# MP-Power.net
KiCad netlist of a schematic drawn in Altium Designer
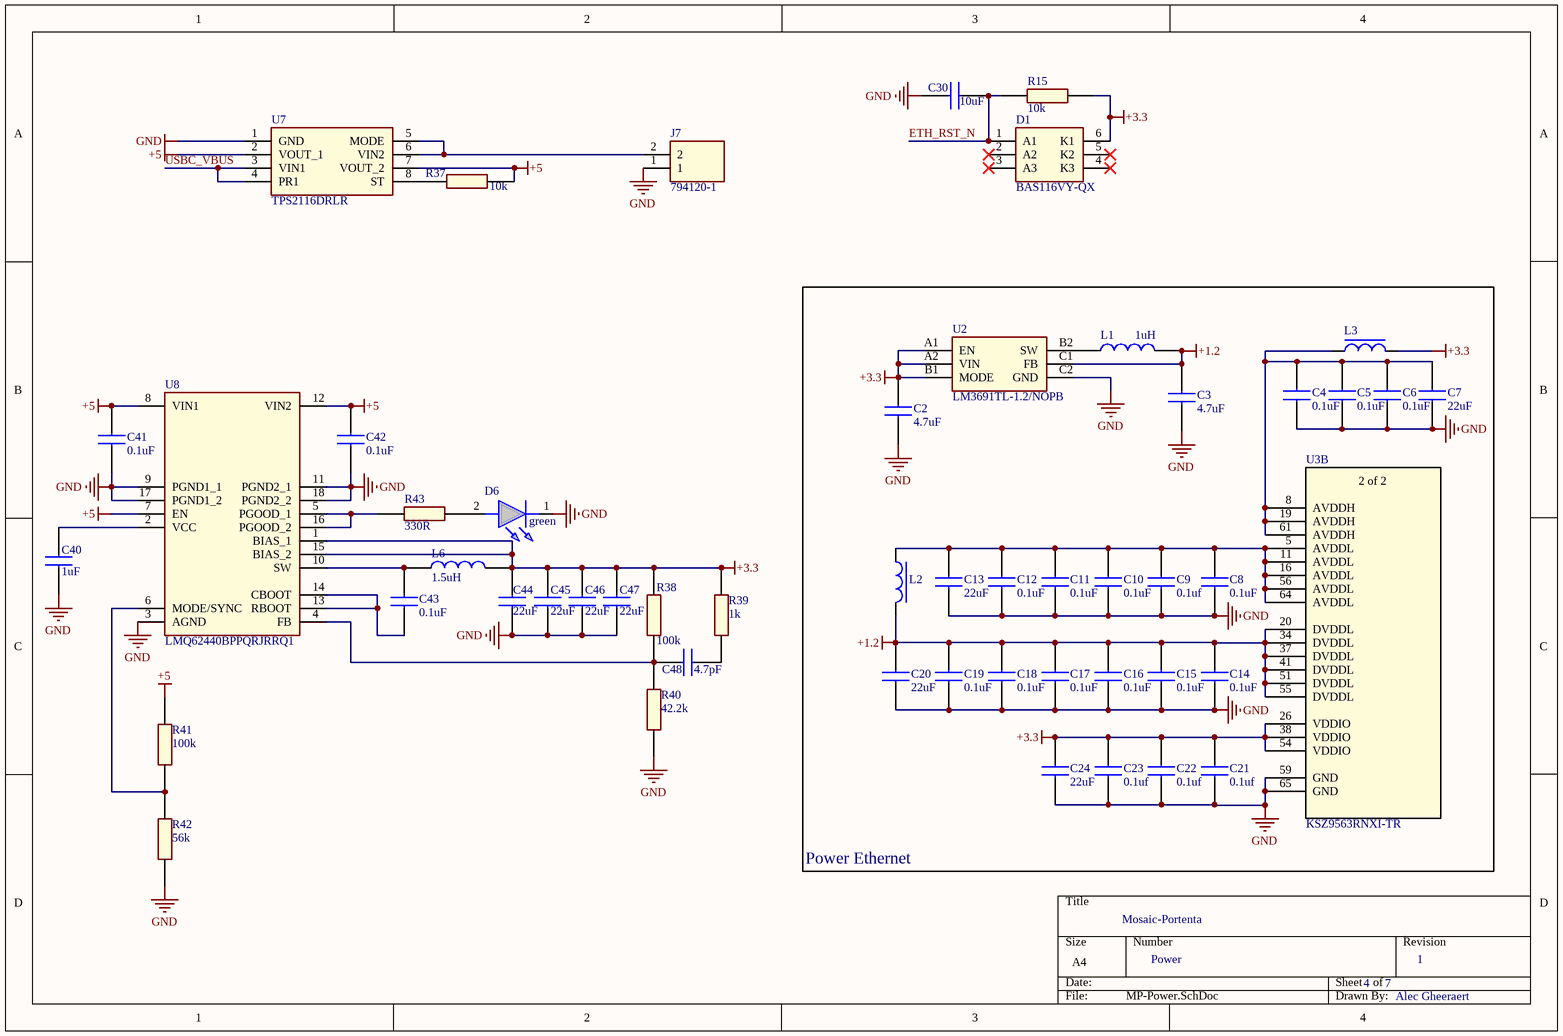
[diagram p0: MP-Power.SchDoc]

(export (version "E")
  (design (tool "Eeschema 10.0.6"))
  (components
    (comp (ref "C2")
      (value "4.7uF")
      (footprint "CAPC1608X100N")
      (description "0603 4.7µF")
      (fields (field (name "MANUFACTURER") "Walsin") (field (name "TOLERANCE") "20%"))
      (libsource (lib "Ghrt") (part "0603X475M6R3CT"))
    )
    (comp (ref "C3")
      (value "4.7uF")
      (footprint "CAPC1608X100N")
      (description "0603 4.7µF")
      (fields (field (name "MANUFACTURER") "Walsin") (field (name "TOLERANCE") "20%"))
      (libsource (lib "Ghrt") (part "0603X475M6R3CT"))
    )
    (comp (ref "C4")
      (value "0.1uF")
      (footprint "CAPC1005X55N")
      (description "0402I 0.1µF")
      (fields (field (name "MANUFACTURER") "Walsin") (field (name "TOLERANCE") "10%"))
      (libsource (lib "Ghrt") (part "MG15B104K100CT"))
    )
    (comp (ref "C5")
      (value "0.1uF")
      (footprint "CAPC1005X55N")
      (description "0402I 0.1µF")
      (fields (field (name "MANUFACTURER") "Walsin") (field (name "TOLERANCE") "10%"))
      (libsource (lib "Ghrt") (part "MG15B104K100CT"))
    )
    (comp (ref "C6")
      (value "0.1uF")
      (footprint "CAPC1005X55N")
      (description "0402I 0.1µF")
      (fields (field (name "MANUFACTURER") "Walsin") (field (name "TOLERANCE") "10%"))
      (libsource (lib "Ghrt") (part "MG15B104K100CT"))
    )
    (comp (ref "C7")
      (value "22uF")
      (footprint "CAPC2012X145N")
      (description "0805 22µF")
      (fields (field (name "MANUFACTURER") "Walsin") (field (name "TOLERANCE") "10%"))
      (libsource (lib "Ghrt") (part "0805X226K6R3CT"))
    )
    (comp (ref "C8")
      (value "0.1uF")
      (footprint "CAPC1005X55N")
      (description "0402I 0.1µF")
      (fields (field (name "MANUFACTURER") "Walsin") (field (name "TOLERANCE") "10%"))
      (libsource (lib "Ghrt") (part "MG15B104K100CT"))
    )
    (comp (ref "C9")
      (value "0.1uf")
      (footprint "CAPC1005X55N")
      (description "0402I 0.1µF")
      (fields (field (name "MANUFACTURER") "Walsin") (field (name "TOLERANCE") "10%"))
      (libsource (lib "Ghrt") (part "MG15B104K100CT"))
    )
    (comp (ref "C10")
      (value "0.1uF")
      (footprint "CAPC1005X55N")
      (description "0402I 0.1µF")
      (fields (field (name "MANUFACTURER") "Walsin") (field (name "TOLERANCE") "10%"))
      (libsource (lib "Ghrt") (part "MG15B104K100CT"))
    )
    (comp (ref "C11")
      (value "0.1uF")
      (footprint "CAPC1005X55N")
      (description "0402I 0.1µF")
      (fields (field (name "MANUFACTURER") "Walsin") (field (name "TOLERANCE") "10%"))
      (libsource (lib "Ghrt") (part "MG15B104K100CT"))
    )
    (comp (ref "C12")
      (value "0.1uF")
      (footprint "CAPC1005X55N")
      (description "0402I 0.1µF")
      (fields (field (name "MANUFACTURER") "Walsin") (field (name "TOLERANCE") "10%"))
      (libsource (lib "Ghrt") (part "MG15B104K100CT"))
    )
    (comp (ref "C13")
      (value "22uF")
      (footprint "CAPC2012X145N")
      (description "0805 22µF")
      (fields (field (name "MANUFACTURER") "Walsin") (field (name "TOLERANCE") "10%"))
      (libsource (lib "Ghrt") (part "0805X226K6R3CT"))
    )
    (comp (ref "C14")
      (value "0.1uF")
      (footprint "CAPC1005X55N")
      (description "0402I 0.1µF")
      (fields (field (name "MANUFACTURER") "Walsin") (field (name "TOLERANCE") "10%"))
      (libsource (lib "Ghrt") (part "MG15B104K100CT"))
    )
    (comp (ref "C15")
      (value "0.1uF")
      (footprint "CAPC1005X55N")
      (description "0402I 0.1µF")
      (fields (field (name "MANUFACTURER") "Walsin") (field (name "TOLERANCE") "10%"))
      (libsource (lib "Ghrt") (part "MG15B104K100CT"))
    )
    (comp (ref "C16")
      (value "0.1uF")
      (footprint "CAPC1005X55N")
      (description "0402I 0.1µF")
      (fields (field (name "MANUFACTURER") "Walsin") (field (name "TOLERANCE") "10%"))
      (libsource (lib "Ghrt") (part "MG15B104K100CT"))
    )
    (comp (ref "C17")
      (value "0.1uF")
      (footprint "CAPC1005X55N")
      (description "0402I 0.1µF")
      (fields (field (name "MANUFACTURER") "Walsin") (field (name "TOLERANCE") "10%"))
      (libsource (lib "Ghrt") (part "MG15B104K100CT"))
    )
    (comp (ref "C18")
      (value "0.1uF")
      (footprint "CAPC1005X55N")
      (description "0402I 0.1µF")
      (fields (field (name "MANUFACTURER") "Walsin") (field (name "TOLERANCE") "10%"))
      (libsource (lib "Ghrt") (part "MG15B104K100CT"))
    )
    (comp (ref "C19")
      (value "0.1uF")
      (footprint "CAPC1005X55N")
      (description "0402I 0.1µF")
      (fields (field (name "MANUFACTURER") "Walsin") (field (name "TOLERANCE") "10%"))
      (libsource (lib "Ghrt") (part "MG15B104K100CT"))
    )
    (comp (ref "C20")
      (value "22uF")
      (footprint "CAPC2012X145N")
      (description "0805 22µF")
      (fields (field (name "MANUFACTURER") "Walsin") (field (name "TOLERANCE") "10%"))
      (libsource (lib "Ghrt") (part "0805X226K6R3CT"))
    )
    (comp (ref "C21")
      (value "0.1uf")
      (footprint "CAPC1005X55N")
      (description "0402I 0.1µF")
      (fields (field (name "MANUFACTURER") "Walsin") (field (name "TOLERANCE") "10%"))
      (libsource (lib "Ghrt") (part "MG15B104K100CT"))
    )
    (comp (ref "C22")
      (value "0.1uf")
      (footprint "CAPC1005X55N")
      (description "0402I 0.1µF")
      (fields (field (name "MANUFACTURER") "Walsin") (field (name "TOLERANCE") "10%"))
      (libsource (lib "Ghrt") (part "MG15B104K100CT"))
    )
    (comp (ref "C23")
      (value "0.1uf")
      (footprint "CAPC1005X55N")
      (description "0402I 0.1µF")
      (fields (field (name "MANUFACTURER") "Walsin") (field (name "TOLERANCE") "10%"))
      (libsource (lib "Ghrt") (part "MG15B104K100CT"))
    )
    (comp (ref "C24")
      (value "22uF")
      (footprint "CAPC2012X145N")
      (description "0805 22µF")
      (fields (field (name "MANUFACTURER") "Walsin") (field (name "TOLERANCE") "10%"))
      (libsource (lib "Ghrt") (part "0805X226K6R3CT"))
    )
    (comp (ref "C30")
      (value "10uF")
      (footprint "CAPC1608X100N")
      (description "0603 10µF")
      (fields (field (name "MANUFACTURER") "Walsin") (field (name "TOLERANCE") "10%"))
      (libsource (lib "Ghrt") (part "0603X106K6R3CT"))
    )
    (comp (ref "C40")
      (value "1uF")
      (footprint "CAPC1608X100N")
      (description "0603 1µF")
      (fields (field (name "MANUFACTURER") "Walsin") (field (name "TOLERANCE") "10%"))
      (libsource (lib "Ghrt") (part "0603X105K6R3CT"))
    )
    (comp (ref "C41")
      (value "0.1uF")
      (footprint "CAPC2012X145N")
      (description "0805I 0.1µF")
      (fields (field (name "MANUFACTURER") "Walsin") (field (name "TOLERANCE") "10%"))
      (libsource (lib "Ghrt") (part "MG21B104K101CT"))
    )
    (comp (ref "C42")
      (value "0.1uF")
      (footprint "CAPC2012X145N")
      (description "0805I 0.1µF")
      (fields (field (name "MANUFACTURER") "Walsin") (field (name "TOLERANCE") "10%"))
      (libsource (lib "Ghrt") (part "MG21B104K101CT"))
    )
    (comp (ref "C43")
      (value "0.1uF")
      (footprint "CAPC1005X55N")
      (description "0402I 0.1µF")
      (fields (field (name "MANUFACTURER") "Walsin") (field (name "TOLERANCE") "10%"))
      (libsource (lib "Ghrt") (part "MG15B104K100CT"))
    )
    (comp (ref "C44")
      (value "22uF")
      (footprint "CAPC2012X145N")
      (description "0805 22µF")
      (fields (field (name "MANUFACTURER") "Walsin") (field (name "TOLERANCE") "10%"))
      (libsource (lib "Ghrt") (part "0805X226K6R3CT"))
    )
    (comp (ref "C45")
      (value "22uF")
      (footprint "CAPC2012X145N")
      (description "0805 22µF")
      (fields (field (name "MANUFACTURER") "Walsin") (field (name "TOLERANCE") "10%"))
      (libsource (lib "Ghrt") (part "0805X226K6R3CT"))
    )
    (comp (ref "C46")
      (value "22uF")
      (footprint "CAPC2012X145N")
      (description "0805 22µF")
      (fields (field (name "MANUFACTURER") "Walsin") (field (name "TOLERANCE") "10%"))
      (libsource (lib "Ghrt") (part "0805X226K6R3CT"))
    )
    (comp (ref "C47")
      (value "22uF")
      (footprint "CAPC2012X145N")
      (description "0805 22µF")
      (fields (field (name "MANUFACTURER") "Walsin") (field (name "TOLERANCE") "10%"))
      (libsource (lib "Ghrt") (part "0805X226K6R3CT"))
    )
    (comp (ref "C48")
      (value "4.7pF")
      (footprint "CAPC1608X87N")
      (description "0603 4.7pF")
      (fields (field (name "TOLERANCE") "5%") (field (name "MANUFACTURER") "Walsin"))
      (libsource (lib "Ghrt") (part "0603N4R7B500CT"))
    )
    (comp (ref "D1")
      (value "BAS116VY-QX")
      (footprint "BAS116VYQX")
      (description "Triple Diode Array")
      (fields (field (name "MANUFACTURER") "Nexperia"))
      (libsource (lib "Ghrt") (part "BAS116VY-QX"))
    )
    (comp (ref "D6")
      (value "green")
      (footprint "APT1608ZGCAMT")
      (description "0603 Green LED")
      (libsource (lib "Ghrt") (part "APT1608ZGC-AMT"))
    )
    (comp (ref "J7")
      (value "794120-1")
      (footprint "7941201")
      (description "Right Angle PCB Header")
      (libsource (lib "Ghrt") (part "794120-1"))
    )
    (comp (ref "L1")
      (value "1uH")
      (footprint "INDC2016X100N")
      (description "1µH Inductor")
      (fields (field (name "TOLERANCE") "20%") (field (name "MANUFACTURER") "TDK"))
      (libsource (lib "Ghrt") (part "MLP2016H1R0MT0S1"))
    )
    (comp (ref "L2")
      (value "MPZ1608S121ATDH5")
      (footprint "BEADC1608X75N")
      (description "0603I 120ohms Ferrite Bead")
      (fields (field (name "TOLERANCE") "25%") (field (name "MANUFACTURER") "TDK"))
      (libsource (lib "Ghrt") (part "MPZ1608S121ATDH5"))
    )
    (comp (ref "L3")
      (value "MPZ1608S121ATDH5")
      (footprint "BEADC1608X75N")
      (description "0603I 120ohms Ferrite Bead")
      (fields (field (name "TOLERANCE") "25%") (field (name "MANUFACTURER") "TDK"))
      (libsource (lib "Ghrt") (part "MPZ1608S121ATDH5"))
    )
    (comp (ref "L6")
      (value "1.5uH")
      (footprint "INDC1005X55N")
      (description "1.5uH Inductor")
      (libsource (lib "Ghrt") (part "MLF1005G1R5JTD25"))
    )
    (comp (ref "R15")
      (value "10k")
      (footprint "RESC1005X40N")
      (description "0402I 10k")
      (fields (field (name "MANUFACTURER") "Walsin") (field (name "TOLERANCE") "1%"))
      (libsource (lib "") (part "WR04X1002FTL_1"))
    )
    (comp (ref "R37")
      (value "10k")
      (footprint "RESC1005X40N")
      (description "0402I 10k")
      (fields (field (name "MANUFACTURER") "Walsin") (field (name "TOLERANCE") "1%"))
      (libsource (lib "Ghrt") (part "WR04X1002FTL"))
    )
    (comp (ref "R38")
      (value "100k")
      (footprint "RESC1005X40N")
      (description "0402I 100k")
      (fields (field (name "MANUFACTURER") "Walsin") (field (name "TOLERANCE") "1%"))
      (libsource (lib "Ghrt") (part "WR04X1003FTL"))
    )
    (comp (ref "R39")
      (value "1k")
      (footprint "RESC1005X40N")
      (description "0402I 1k")
      (fields (field (name "MANUFACTURER") "Walsin") (field (name "TOLERANCE") "1%"))
      (libsource (lib "Ghrt") (part "WR04X1001FTL"))
    )
    (comp (ref "R40")
      (value "42.2k")
      (footprint "RESC1005X40N")
      (description "0402I 42.2k")
      (fields (field (name "TOLERANCE") "1%") (field (name "MANUFACTURER") "Walsin"))
      (libsource (lib "Ghrt") (part "WR04X4222FTL"))
    )
    (comp (ref "R41")
      (value "100k")
      (footprint "RESC1005X40N")
      (description "0402I 100k")
      (fields (field (name "MANUFACTURER") "Walsin") (field (name "TOLERANCE") "1%"))
      (libsource (lib "") (part "WR04X1003FTL_1"))
    )
    (comp (ref "R42")
      (value "56k")
      (footprint "RESC1005X40N")
      (description "0402I 56k")
      (fields (field (name "TOLERANCE") "1%") (field (name "MANUFACTURER") "Walsin"))
      (libsource (lib "Ghrt") (part "WR04X5602FTL"))
    )
    (comp (ref "R43")
      (value "330R")
      (footprint "RESC1005X40N")
      (description "0402I 330")
      (fields (field (name "TOLERANCE") "1%") (field (name "MANUFACTURER") "Walsin"))
      (libsource (lib "Ghrt") (part "WR04X3300FTL"))
    )
    (comp (ref "U2")
      (value "LM3691TL-1.2/NOPB")
      (footprint "BGA6C50P2X3_126X156X68")
      (description "1.2V 1A Buck Converter")
      (fields (field (name "MANUFACTURER") "Texas Instruments"))
      (libsource (lib "Ghrt") (part "LM3691TL-1.2_NOPB"))
    )
    (comp (ref "U3")
      (value "KSZ9563RNXI-TR")
      (footprint "VQFN64_NX_MCH")
      (description "3-Port Gigabit Ethernet Switch")
      (fields (field (name "MANUFACTURER") "Texas Instruments"))
      (libsource (lib "Ghrt") (part "KSZ9563RNXI-TR"))
    )
    (comp (ref "U7")
      (value "TPS2116DRLR")
      (footprint "SOTFL50P160X60-8N")
      (description "2.5A Power Multiplexer")
      (fields (field (name "MANUFACTURER") "Texas Instruments"))
      (libsource (lib "Ghrt") (part "TPS2116DRLR"))
    )
    (comp (ref "U8")
      (value "LMQ62440BPPQRJRRQ1")
      (footprint "LMQ62440BPPQRJRRQ1")
      (description "3.3V 4A Switching Voltage Regulator")
      (fields (field (name "MANUFACTURER") "Texas Instruments"))
      (libsource (lib "Ghrt") (part "LMQ62440BPPQRJRRQ1"))
    )
  )
  (nets
    (net (code "1") (name "+1.2") (class "Default")
      (node (ref "C14") (pin "1") (pinfunction "1_1") (pintype "passive"))
      (node (ref "C15") (pin "1") (pinfunction "1_1") (pintype "passive"))
      (node (ref "C16") (pin "1") (pinfunction "1_1") (pintype "passive"))
      (node (ref "C17") (pin "1") (pinfunction "1_1") (pintype "passive"))
      (node (ref "C18") (pin "1") (pinfunction "1_1") (pintype "passive"))
      (node (ref "C19") (pin "1") (pinfunction "1_1") (pintype "passive"))
      (node (ref "C20") (pin "1") (pinfunction "1_1") (pintype "passive"))
      (node (ref "C3") (pin "1") (pinfunction "1_1") (pintype "passive"))
      (node (ref "L1") (pin "2") (pinfunction "2_2") (pintype "passive"))
      (node (ref "L2") (pin "2") (pinfunction "2_2") (pintype "passive"))
      (node (ref "U2") (pin "C1") (pinfunction "FB_C1") (pintype "passive"))
      (node (ref "U3") (pin "20") (pinfunction "DVDDL_20") (pintype "power_in"))
      (node (ref "U3") (pin "34") (pinfunction "DVDDL_34") (pintype "power_in"))
      (node (ref "U3") (pin "37") (pinfunction "DVDDL_37") (pintype "power_in"))
      (node (ref "U3") (pin "41") (pinfunction "DVDDL_41") (pintype "power_in"))
      (node (ref "U3") (pin "51") (pinfunction "DVDDL_51") (pintype "power_in"))
      (node (ref "U3") (pin "55") (pinfunction "DVDDL_55") (pintype "power_in"))
    )
    (net (code "2") (name "+3.3") (class "Default")
      (node (ref "C2") (pin "1") (pinfunction "1_1") (pintype "passive"))
      (node (ref "C21") (pin "1") (pinfunction "1_1") (pintype "passive"))
      (node (ref "C22") (pin "1") (pinfunction "1_1") (pintype "passive"))
      (node (ref "C23") (pin "1") (pinfunction "1_1") (pintype "passive"))
      (node (ref "C24") (pin "1") (pinfunction "1_1") (pintype "passive"))
      (node (ref "C44") (pin "1") (pinfunction "1_1") (pintype "passive"))
      (node (ref "C45") (pin "1") (pinfunction "1_1") (pintype "passive"))
      (node (ref "C46") (pin "1") (pinfunction "1_1") (pintype "passive"))
      (node (ref "C47") (pin "1") (pinfunction "1_1") (pintype "passive"))
      (node (ref "D1") (pin "6") (pinfunction "K1_6") (pintype "passive"))
      (node (ref "L3") (pin "2") (pinfunction "2_2") (pintype "passive"))
      (node (ref "L6") (pin "2") (pinfunction "2_2") (pintype "passive"))
      (node (ref "R15") (pin "1") (pinfunction "1_1") (pintype "passive"))
      (node (ref "R38") (pin "1") (pinfunction "1_1") (pintype "passive"))
      (node (ref "R39") (pin "2") (pinfunction "2_2") (pintype "passive"))
      (node (ref "U2") (pin "A1") (pinfunction "EN_A1") (pintype "passive"))
      (node (ref "U2") (pin "A2") (pinfunction "VIN_A2") (pintype "passive"))
      (node (ref "U2") (pin "B1") (pinfunction "MODE_B1") (pintype "passive"))
      (node (ref "U3") (pin "26") (pinfunction "VDDIO_26") (pintype "power_in"))
      (node (ref "U3") (pin "38") (pinfunction "VDDIO_38") (pintype "power_in"))
      (node (ref "U3") (pin "54") (pinfunction "VDDIO_54") (pintype "power_in"))
      (node (ref "U8") (pin "1") (pinfunction "BIAS_1_1") (pintype "passive"))
      (node (ref "U8") (pin "15") (pinfunction "BIAS_2_15") (pintype "passive"))
    )
    (net (code "3") (name "+5") (class "Default")
      (node (ref "C41") (pin "1") (pinfunction "1_1") (pintype "passive"))
      (node (ref "C42") (pin "1") (pinfunction "1_1") (pintype "passive"))
      (node (ref "R37") (pin "2") (pinfunction "2_2") (pintype "passive"))
      (node (ref "R41") (pin "2") (pinfunction "2_2") (pintype "passive"))
      (node (ref "U7") (pin "2") (pinfunction "VOUT_1_2") (pintype "passive"))
      (node (ref "U7") (pin "7") (pinfunction "VOUT_2_7") (pintype "passive"))
      (node (ref "U8") (pin "12") (pinfunction "VIN2_12") (pintype "passive"))
      (node (ref "U8") (pin "7") (pinfunction "EN_7") (pintype "passive"))
      (node (ref "U8") (pin "8") (pinfunction "VIN1_8") (pintype "passive"))
    )
    (net (code "4") (name "/ETH_RST_N") (class "Default")
      (node (ref "C30") (pin "1") (pinfunction "1_1") (pintype "passive"))
      (node (ref "D1") (pin "1") (pinfunction "A1_1") (pintype "passive"))
      (node (ref "R15") (pin "2") (pinfunction "2_2") (pintype "passive"))
    )
    (net (code "5") (name "/USBC_VBUS") (class "Default")
      (node (ref "U7") (pin "3") (pinfunction "VIN1_3") (pintype "passive"))
      (node (ref "U7") (pin "4") (pinfunction "PR1_4") (pintype "passive"))
    )
    (net (code "6") (name "GND") (class "Default")
      (node (ref "C10") (pin "2") (pinfunction "2_2") (pintype "passive"))
      (node (ref "C11") (pin "2") (pinfunction "2_2") (pintype "passive"))
      (node (ref "C12") (pin "2") (pinfunction "2_2") (pintype "passive"))
      (node (ref "C13") (pin "2") (pinfunction "2_2") (pintype "passive"))
      (node (ref "C14") (pin "2") (pinfunction "2_2") (pintype "passive"))
      (node (ref "C15") (pin "2") (pinfunction "2_2") (pintype "passive"))
      (node (ref "C16") (pin "2") (pinfunction "2_2") (pintype "passive"))
      (node (ref "C17") (pin "2") (pinfunction "2_2") (pintype "passive"))
      (node (ref "C18") (pin "2") (pinfunction "2_2") (pintype "passive"))
      (node (ref "C19") (pin "2") (pinfunction "2_2") (pintype "passive"))
      (node (ref "C2") (pin "2") (pinfunction "2_2") (pintype "passive"))
      (node (ref "C20") (pin "2") (pinfunction "2_2") (pintype "passive"))
      (node (ref "C21") (pin "2") (pinfunction "2_2") (pintype "passive"))
      (node (ref "C22") (pin "2") (pinfunction "2_2") (pintype "passive"))
      (node (ref "C23") (pin "2") (pinfunction "2_2") (pintype "passive"))
      (node (ref "C24") (pin "2") (pinfunction "2_2") (pintype "passive"))
      (node (ref "C3") (pin "2") (pinfunction "2_2") (pintype "passive"))
      (node (ref "C30") (pin "2") (pinfunction "2_2") (pintype "passive"))
      (node (ref "C4") (pin "2") (pinfunction "2_2") (pintype "passive"))
      (node (ref "C40") (pin "2") (pinfunction "2_2") (pintype "passive"))
      (node (ref "C41") (pin "2") (pinfunction "2_2") (pintype "passive"))
      (node (ref "C42") (pin "2") (pinfunction "2_2") (pintype "passive"))
      (node (ref "C44") (pin "2") (pinfunction "2_2") (pintype "passive"))
      (node (ref "C45") (pin "2") (pinfunction "2_2") (pintype "passive"))
      (node (ref "C46") (pin "2") (pinfunction "2_2") (pintype "passive"))
      (node (ref "C47") (pin "2") (pinfunction "2_2") (pintype "passive"))
      (node (ref "C5") (pin "2") (pinfunction "2_2") (pintype "passive"))
      (node (ref "C6") (pin "2") (pinfunction "2_2") (pintype "passive"))
      (node (ref "C7") (pin "2") (pinfunction "2_2") (pintype "passive"))
      (node (ref "C8") (pin "2") (pinfunction "2_2") (pintype "passive"))
      (node (ref "C9") (pin "2") (pinfunction "2_2") (pintype "passive"))
      (node (ref "D6") (pin "1") (pinfunction "K_1") (pintype "passive"))
      (node (ref "J7") (pin "1") (pinfunction "1_1") (pintype "passive"))
      (node (ref "R40") (pin "2") (pinfunction "2_2") (pintype "passive"))
      (node (ref "R42") (pin "2") (pinfunction "2_2") (pintype "passive"))
      (node (ref "U2") (pin "C2") (pinfunction "GND_C2") (pintype "passive"))
      (node (ref "U3") (pin "59") (pinfunction "GND_59") (pintype "power_in"))
      (node (ref "U3") (pin "65") (pinfunction "GND_65") (pintype "power_in"))
      (node (ref "U7") (pin "1") (pinfunction "GND_1") (pintype "passive"))
      (node (ref "U8") (pin "11") (pinfunction "PGND2_1_11") (pintype "passive"))
      (node (ref "U8") (pin "17") (pinfunction "PGND1_2_17") (pintype "passive"))
      (node (ref "U8") (pin "18") (pinfunction "PGND2_2_18") (pintype "passive"))
      (node (ref "U8") (pin "3") (pinfunction "AGND_3") (pintype "passive"))
      (node (ref "U8") (pin "9") (pinfunction "PGND1_1_9") (pintype "passive"))
    )
    (net (code "7") (name "Net-(C4-Pad1)") (class "Default")
      (node (ref "C4") (pin "1") (pinfunction "1_1") (pintype "passive"))
      (node (ref "C5") (pin "1") (pinfunction "1_1") (pintype "passive"))
      (node (ref "C6") (pin "1") (pinfunction "1_1") (pintype "passive"))
      (node (ref "C7") (pin "1") (pinfunction "1_1") (pintype "passive"))
      (node (ref "L3") (pin "1") (pinfunction "1_1") (pintype "passive"))
      (node (ref "U3") (pin "19") (pinfunction "AVDDH_19") (pintype "power_in"))
      (node (ref "U3") (pin "61") (pinfunction "AVDDH_61") (pintype "power_in"))
      (node (ref "U3") (pin "8") (pinfunction "AVDDH_8") (pintype "power_in"))
    )
    (net (code "8") (name "Net-(C10-Pad1)") (class "Default")
      (node (ref "C10") (pin "1") (pinfunction "1_1") (pintype "passive"))
      (node (ref "C11") (pin "1") (pinfunction "1_1") (pintype "passive"))
      (node (ref "C12") (pin "1") (pinfunction "1_1") (pintype "passive"))
      (node (ref "C13") (pin "1") (pinfunction "1_1") (pintype "passive"))
      (node (ref "C8") (pin "1") (pinfunction "1_1") (pintype "passive"))
      (node (ref "C9") (pin "1") (pinfunction "1_1") (pintype "passive"))
      (node (ref "L2") (pin "1") (pinfunction "1_1") (pintype "passive"))
      (node (ref "U3") (pin "11") (pinfunction "AVDDL_11") (pintype "power_in"))
      (node (ref "U3") (pin "16") (pinfunction "AVDDL_16") (pintype "power_in"))
      (node (ref "U3") (pin "5") (pinfunction "AVDDL_5") (pintype "power_in"))
      (node (ref "U3") (pin "56") (pinfunction "AVDDL_56") (pintype "power_in"))
      (node (ref "U3") (pin "64") (pinfunction "AVDDL_64") (pintype "power_in"))
    )
    (net (code "9") (name "Net-(C48-Pad2)") (class "Default")
      (node (ref "C48") (pin "2") (pinfunction "2_2") (pintype "passive"))
      (node (ref "R39") (pin "1") (pinfunction "1_1") (pintype "passive"))
    )
    (net (code "10") (name "Net-(D6-A)") (class "Default")
      (node (ref "D6") (pin "2") (pinfunction "A_2") (pintype "passive"))
      (node (ref "R43") (pin "2") (pinfunction "2_2") (pintype "passive"))
    )
    (net (code "11") (name "Net-(U2-SW)") (class "Default")
      (node (ref "L1") (pin "1") (pinfunction "1_1") (pintype "passive"))
      (node (ref "U2") (pin "B2") (pinfunction "SW_B2") (pintype "passive"))
    )
    (net (code "12") (name "Net-(U7-MODE)") (class "Default")
      (node (ref "J7") (pin "2") (pinfunction "2_2") (pintype "passive"))
      (node (ref "U7") (pin "5") (pinfunction "MODE_5") (pintype "passive"))
      (node (ref "U7") (pin "6") (pinfunction "VIN2_6") (pintype "passive"))
    )
    (net (code "13") (name "Net-(U7-ST)") (class "Default")
      (node (ref "R37") (pin "1") (pinfunction "1_1") (pintype "passive"))
      (node (ref "U7") (pin "8") (pinfunction "ST_8") (pintype "passive"))
    )
    (net (code "14") (name "Net-(U8-CBOOT)") (class "Default")
      (node (ref "C43") (pin "2") (pinfunction "2_2") (pintype "passive"))
      (node (ref "U8") (pin "13") (pinfunction "RBOOT_13") (pintype "passive"))
      (node (ref "U8") (pin "14") (pinfunction "CBOOT_14") (pintype "passive"))
    )
    (net (code "15") (name "Net-(U8-FB)") (class "Default")
      (node (ref "C48") (pin "1") (pinfunction "1_1") (pintype "passive"))
      (node (ref "R38") (pin "2") (pinfunction "2_2") (pintype "passive"))
      (node (ref "R40") (pin "1") (pinfunction "1_1") (pintype "passive"))
      (node (ref "U8") (pin "4") (pinfunction "FB_4") (pintype "passive"))
    )
    (net (code "16") (name "Net-(U8-MODE{slash}SYNC)") (class "Default")
      (node (ref "R41") (pin "1") (pinfunction "1_1") (pintype "passive"))
      (node (ref "R42") (pin "1") (pinfunction "1_1") (pintype "passive"))
      (node (ref "U8") (pin "6") (pinfunction "MODE/SYNC_6") (pintype "passive"))
    )
    (net (code "17") (name "Net-(U8-PGOOD_1)") (class "Default")
      (node (ref "R43") (pin "1") (pinfunction "1_1") (pintype "passive"))
      (node (ref "U8") (pin "16") (pinfunction "PGOOD_2_16") (pintype "passive"))
      (node (ref "U8") (pin "5") (pinfunction "PGOOD_1_5") (pintype "passive"))
    )
    (net (code "18") (name "Net-(U8-SW)") (class "Default")
      (node (ref "C43") (pin "1") (pinfunction "1_1") (pintype "passive"))
      (node (ref "L6") (pin "1") (pinfunction "1_1") (pintype "passive"))
      (node (ref "U8") (pin "10") (pinfunction "SW_10") (pintype "passive"))
    )
    (net (code "19") (name "Net-(U8-VCC)") (class "Default")
      (node (ref "C40") (pin "1") (pinfunction "1_1") (pintype "passive"))
      (node (ref "U8") (pin "2") (pinfunction "VCC_2") (pintype "passive"))
    )
    (net (code "20") (name "unconnected-(D1-A2-Pad2)") (class "Default")
      (node (ref "D1") (pin "2") (pinfunction "A2_2") (pintype "passive+no_connect"))
    )
    (net (code "21") (name "unconnected-(D1-A3-Pad3)") (class "Default")
      (node (ref "D1") (pin "3") (pinfunction "A3_3") (pintype "passive+no_connect"))
    )
    (net (code "22") (name "unconnected-(D1-K2-Pad5)") (class "Default")
      (node (ref "D1") (pin "5") (pinfunction "K2_5") (pintype "passive+no_connect"))
    )
    (net (code "23") (name "unconnected-(D1-K3-Pad4)") (class "Default")
      (node (ref "D1") (pin "4") (pinfunction "K3_4") (pintype "passive+no_connect"))
    )
  )
)
